# optic_fiber_tx.net
KiCad netlist of a schematic drawn in Altium Designer
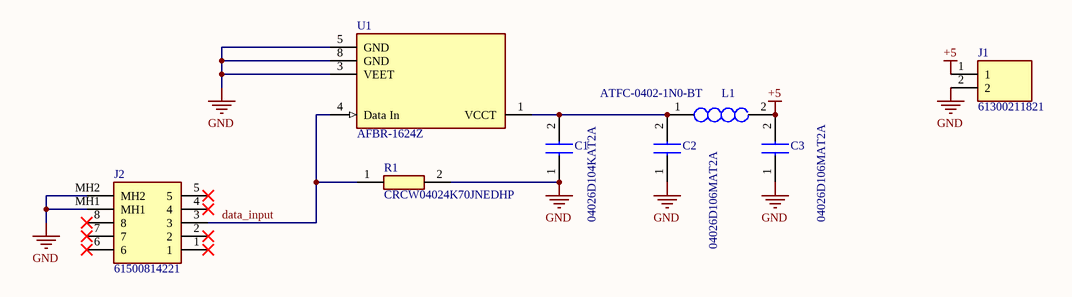
[diagram p0: optic_fiber_tx.SchDoc]

(export (version "E")
  (design (tool "Eeschema 10.0.6"))
  (components
    (comp (ref "C1")
      (value "04026D104KAT2A")
      (footprint "optic_fiber_tx:CAPC1005X56N")
      (description "Capacitor")
      (fields (field (name "MOUSER PART NUMBER") "581-04026D104KAT2A"))
      (libsource (lib "*") (part "04026D104KAT2A"))
    )
    (comp (ref "C2")
      (value "04026D106MAT2A")
      (footprint "optic_fiber_tx:CAPC1005X56N")
      (description "Capacitor")
      (fields (field (name "MOUSER PART NUMBER") "581-04026D106MAT2A"))
      (libsource (lib "*") (part "04026D106MAT2A"))
    )
    (comp (ref "C3")
      (value "04026D106MAT2A")
      (footprint "optic_fiber_tx:CAPC1005X56N")
      (description "Capacitor")
      (fields (field (name "MOUSER PART NUMBER") "581-04026D106MAT2A"))
      (libsource (lib "*") (part "04026D106MAT2A"))
    )
    (comp (ref "J1")
      (value "61300211821")
      (footprint "optic_fiber_tx:61300211821")
      (description "Connector")
      (libsource (lib "*") (part "61300211821"))
    )
    (comp (ref "J2")
      (value "61500814221")
      (footprint "optic_fiber_tx:61500814221")
      (description "Connector")
      (fields (field (name "MOUSER PART NUMBER") "710-61500814221"))
      (libsource (lib "*") (part "61500814221"))
    )
    (comp (ref "L1")
      (value "ATFC-0402-1N0-BT")
      (footprint "optic_fiber_tx:INDC1005X37N")
      (description "Inductor")
      (fields (field (name "MOUSER PART NUMBER") "815-ATFC-0402-1N0-BT"))
      (libsource (lib "*") (part "ATFC-0402-1N0-BT"))
    )
    (comp (ref "R1")
      (value "CRCW04024K70JNEDHP")
      (footprint "optic_fiber_tx:RESC1005X40N")
      (description "Resistor")
      (fields (field (name "MOUSER PART NUMBER") "71-CRCW04024K70JNEDH"))
      (libsource (lib "*") (part "CRCW04024K70JNEDHP"))
    )
    (comp (ref "U1")
      (value "AFBR-1624Z")
      (footprint "FP-AFBR-1624Z-MFG")
      (description "TXRX OPT 650NM 1MM POF")
      (libsource (lib "Altium Content Vault") (part "a9f1705cd51eecd48085a583a3b33b1"))
    )
  )
  (nets
    (net (code "1") (name "+5") (class "Default")
      (node (ref "C3") (pin "2") (pinfunction "2_2") (pintype "passive"))
      (node (ref "J1") (pin "1") (pinfunction "1_1") (pintype "passive"))
      (node (ref "L1") (pin "2") (pinfunction "2_2") (pintype "passive"))
    )
    (net (code "2") (name "/data_input") (class "Default")
      (node (ref "J2") (pin "3") (pinfunction "3_3") (pintype "passive"))
      (node (ref "R1") (pin "1") (pinfunction "1_1") (pintype "passive"))
      (node (ref "U1") (pin "4") (pinfunction "Data_In_4") (pintype "input"))
    )
    (net (code "3") (name "GND") (class "Default")
      (node (ref "C1") (pin "1") (pinfunction "1_1") (pintype "passive"))
      (node (ref "C2") (pin "1") (pinfunction "1_1") (pintype "passive"))
      (node (ref "C3") (pin "1") (pinfunction "1_1") (pintype "passive"))
      (node (ref "J1") (pin "2") (pinfunction "2_2") (pintype "passive"))
      (node (ref "J2") (pin "MH1") (pinfunction "MH1_MH1") (pintype "passive"))
      (node (ref "J2") (pin "MH2") (pinfunction "MH2_MH2") (pintype "passive"))
      (node (ref "R1") (pin "2") (pinfunction "2_2") (pintype "passive"))
      (node (ref "U1") (pin "3") (pinfunction "VEET_3") (pintype "power_in"))
      (node (ref "U1") (pin "5") (pinfunction "GND_5") (pintype "power_in"))
      (node (ref "U1") (pin "8") (pinfunction "GND_8") (pintype "power_in"))
    )
    (net (code "4") (name "Net-(U1-VCCT)") (class "Default")
      (node (ref "C1") (pin "2") (pinfunction "2_2") (pintype "passive"))
      (node (ref "C2") (pin "2") (pinfunction "2_2") (pintype "passive"))
      (node (ref "L1") (pin "1") (pinfunction "1_1") (pintype "passive"))
      (node (ref "U1") (pin "1") (pinfunction "VCCT_1") (pintype "power_in"))
    )
    (net (code "5") (name "unconnected-(J2-Pad1)") (class "Default")
      (node (ref "J2") (pin "1") (pinfunction "1_1") (pintype "passive+no_connect"))
    )
    (net (code "6") (name "unconnected-(J2-Pad2)") (class "Default")
      (node (ref "J2") (pin "2") (pinfunction "2_2") (pintype "passive+no_connect"))
    )
    (net (code "7") (name "unconnected-(J2-Pad4)") (class "Default")
      (node (ref "J2") (pin "4") (pinfunction "4_4") (pintype "passive+no_connect"))
    )
    (net (code "8") (name "unconnected-(J2-Pad5)") (class "Default")
      (node (ref "J2") (pin "5") (pinfunction "5_5") (pintype "passive+no_connect"))
    )
    (net (code "9") (name "unconnected-(J2-Pad6)") (class "Default")
      (node (ref "J2") (pin "6") (pinfunction "6_6") (pintype "passive+no_connect"))
    )
    (net (code "10") (name "unconnected-(J2-Pad7)") (class "Default")
      (node (ref "J2") (pin "7") (pinfunction "7_7") (pintype "passive+no_connect"))
    )
    (net (code "11") (name "unconnected-(J2-Pad8)") (class "Default")
      (node (ref "J2") (pin "8") (pinfunction "8_8") (pintype "passive+no_connect"))
    )
  )
)
